# Drive_Board_Schematic_3_motors_SchDocFin.net
KiCad netlist of a schematic drawn in Altium Designer
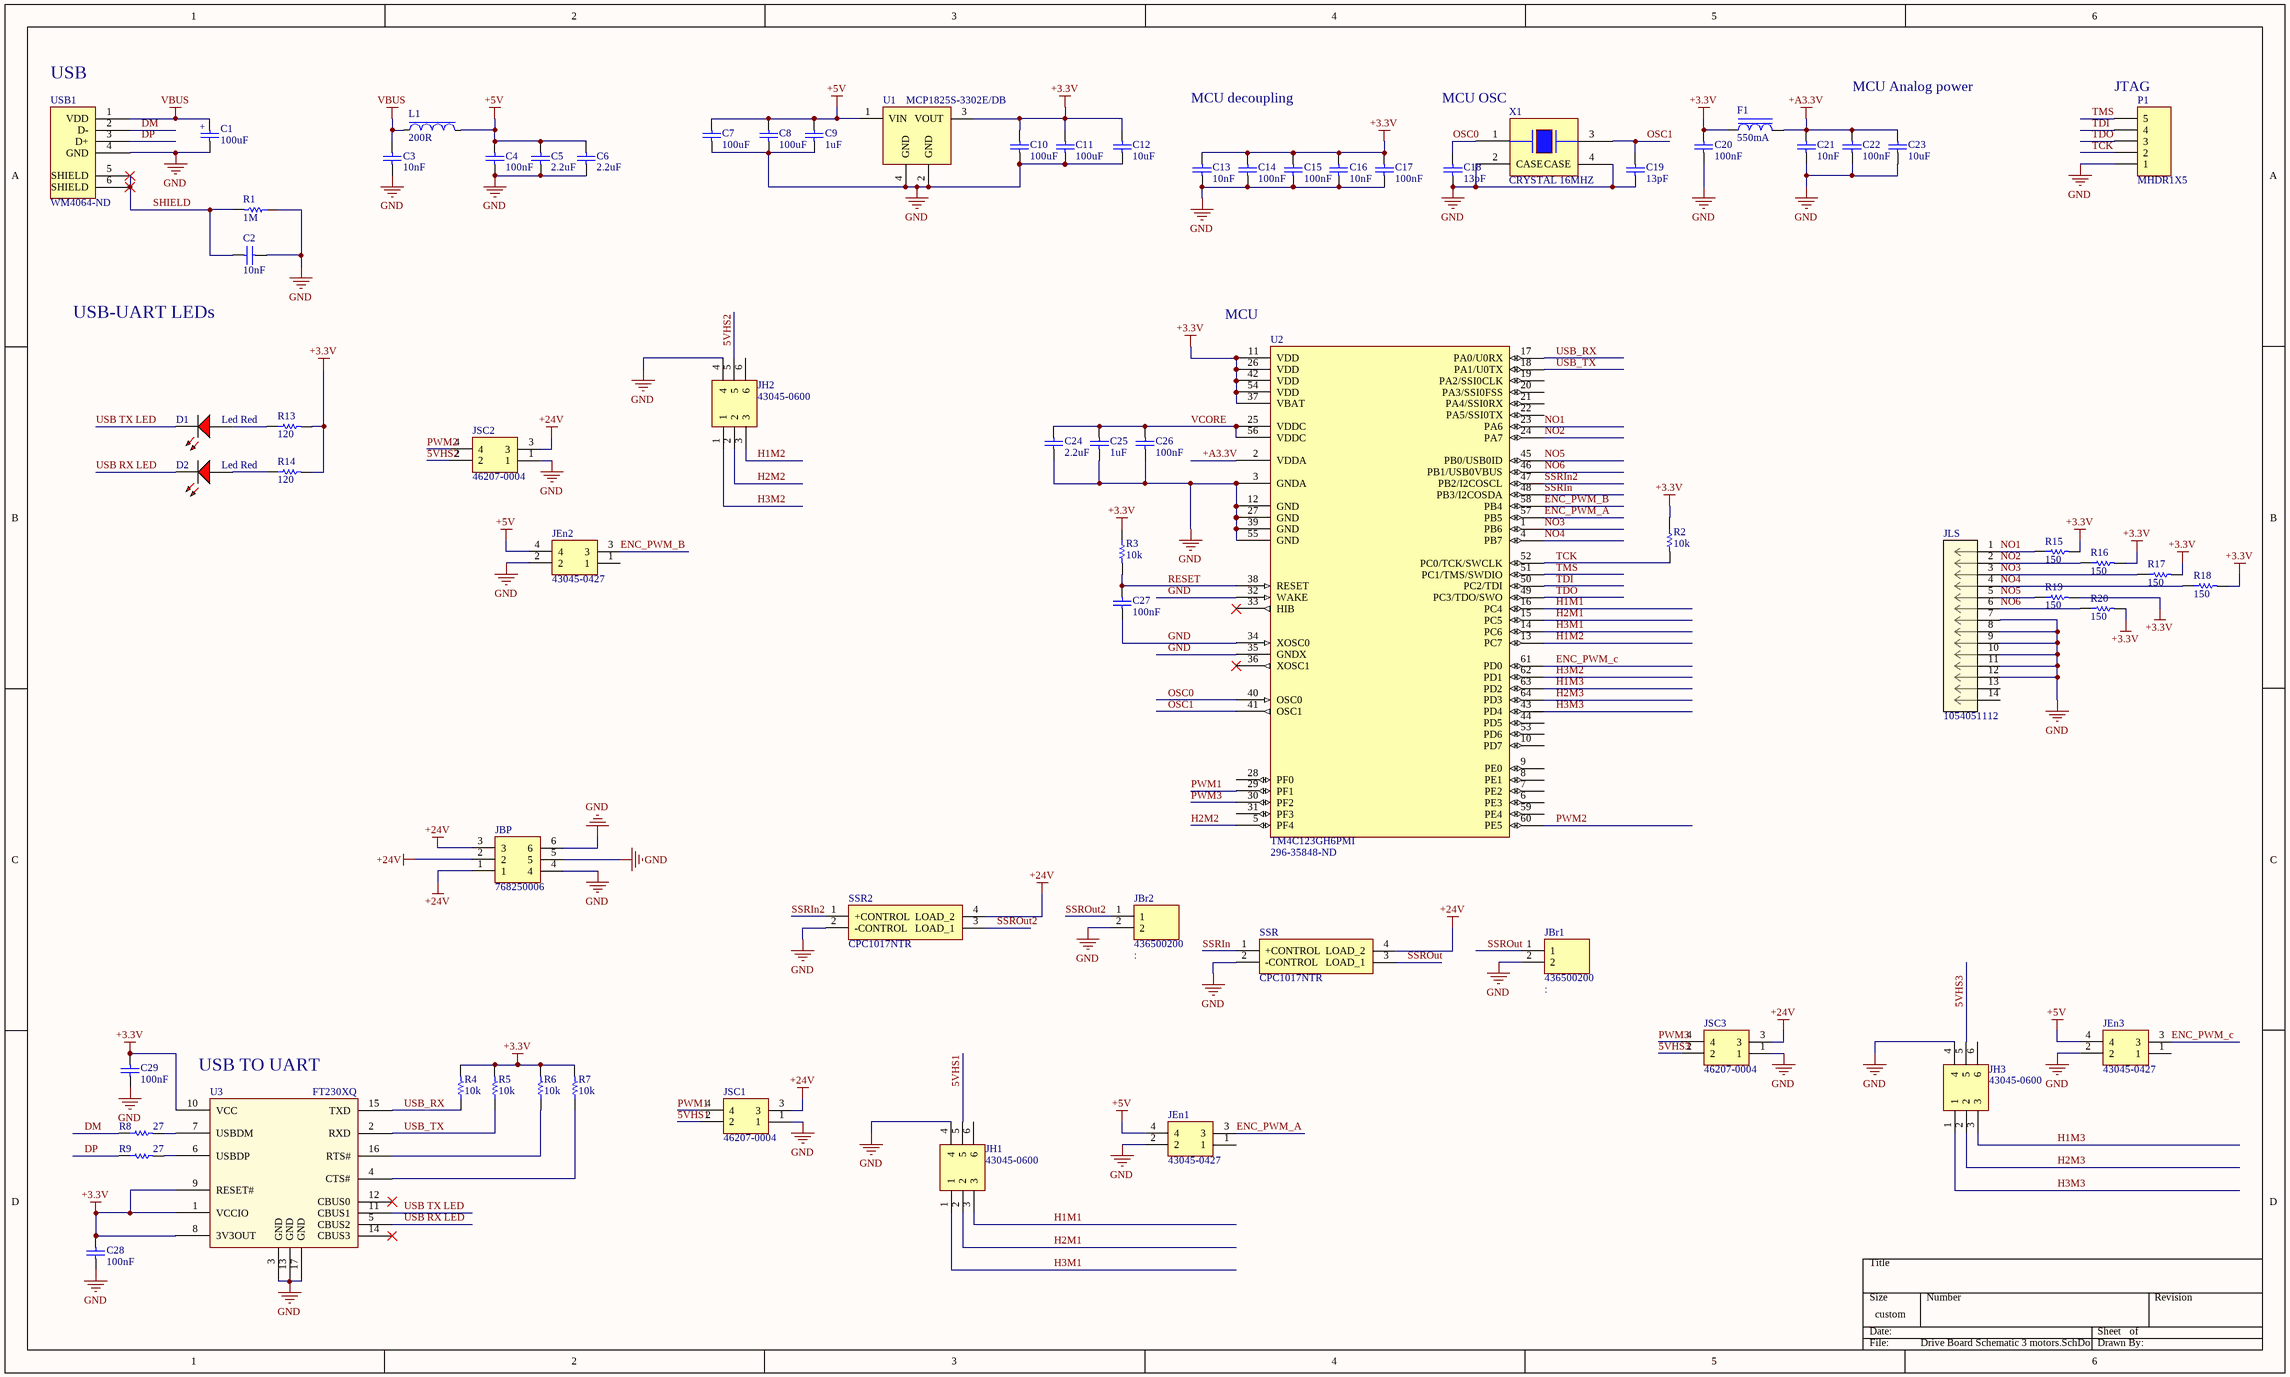
[diagram p0: Drive Board Schematic 3 motors.SchDocFinal.SchDoc]

(export (version "E")
  (design (tool "Eeschema 10.0.6"))
  (components
    (comp (ref "C1")
      (value "100uF")
      (footprint "CapAlu6.3mmx12.5mm")
      (description "Capacitor 35v 100uF 6.3mm")
      (fields
        (field (name "MANUFACTURER") "Nichicon")
        (field (name "MANUFACTURER PART NUMBER") "UHV1V101MED")
      )
      (libsource (lib "Capacitors") (part "100uF_35v_6.3x12.5"))
    )
    (comp (ref "C2")
      (value "10nF")
      (footprint "CAP_1206")
      (description "CAP CER 10000PF 500V X7R 1206")
      (fields
        (field (name "MANUFACTURER") "Samsung Electro-Mechanics America, Inc")
        (field (name "MANUFACTURER PART NUMBER") "CL31B103KGFNNNE")
      )
      (libsource (lib "Capacitors") (part "10nF_500V_1206"))
    )
    (comp (ref "C3")
      (value "10nF")
      (footprint "CAP_0402_M")
      (description "CAP CER 10000PF 50V 10% X7R 0402")
      (fields
        (field (name "MANUFACTURER") "Kemet")
        (field (name "MANUFACTURER PART NUMBER") "C0402C103K5RACTU")
      )
      (libsource (lib "Capacitors") (part "10nF_50V_0402"))
    )
    (comp (ref "C4")
      (value "100nF")
      (footprint "CAP_0402_M")
      (description "CAP CER 100NF 50V 20% X5R 0402")
      (fields
        (field (name "MANUFACTURER") "TDK Corporation")
        (field (name "MANUFACTURER PART NUMBER") "C1005X5R1H104M050BB")
      )
      (libsource (lib "Capacitors") (part "100nF_50V_0402"))
    )
    (comp (ref "C5")
      (value "2.2uF")
      (footprint "CAP_0402_M")
      (description "CAP CER 2.2UF 10V 20% X5R 0402")
      (fields
        (field (name "MANUFACTURER") "Taiyo Yuden")
        (field (name "MANUFACTURER PART NUMBER") "LMK105BJ225MV-F")
      )
      (libsource (lib "Capacitors") (part "2.2uF_10V_0402"))
    )
    (comp (ref "C6")
      (value "2.2uF")
      (footprint "CAP_0402_M")
      (description "CAP CER 2.2UF 10V 20% X5R 0402")
      (fields
        (field (name "MANUFACTURER") "Taiyo Yuden")
        (field (name "MANUFACTURER PART NUMBER") "LMK105BJ225MV-F")
      )
      (libsource (lib "Capacitors") (part "2.2uF_10V_0402"))
    )
    (comp (ref "C7")
      (value "100uF")
      (footprint "CAP_1206")
      (description "CAP CER 100UF 6.3V X5R 1206")
      (fields
        (field (name "MANUFACTURER") "Murata Electronics North America")
        (field (name "MANUFACTURER PART NUMBER") "GRM31CR60J107ME39L")
      )
      (libsource (lib "Capacitors") (part "100uF_6.3v_1206_X5R"))
    )
    (comp (ref "C8")
      (value "100uF")
      (footprint "CAP_1206")
      (description "CAP CER 100UF 6.3V X5R 1206")
      (fields
        (field (name "MANUFACTURER") "Murata Electronics North America")
        (field (name "MANUFACTURER PART NUMBER") "GRM31CR60J107ME39L")
      )
      (libsource (lib "Capacitors") (part "100uF_6.3v_1206_X5R"))
    )
    (comp (ref "C9")
      (value "1uF")
      (footprint "CAP_0402_M")
      (description "CAP CER 1UF 25V 10% X5R 0402")
      (fields
        (field (name "MANUFACTURER") "TDK Corporation")
        (field (name "MANUFACTURER PART NUMBER") "C1005X5R1E105K050BC")
      )
      (libsource (lib "Capacitors") (part "1uF_25V_0402"))
    )
    (comp (ref "C10")
      (value "100uF")
      (footprint "CAP_1206")
      (description "CAP CER 100UF 6.3V X5R 1206")
      (fields
        (field (name "MANUFACTURER") "Murata Electronics North America")
        (field (name "MANUFACTURER PART NUMBER") "GRM31CR60J107ME39L")
      )
      (libsource (lib "Capacitors") (part "100uF_6.3v_1206_X5R"))
    )
    (comp (ref "C11")
      (value "100uF")
      (footprint "CAP_1206")
      (description "CAP CER 100UF 6.3V X5R 1206")
      (fields
        (field (name "MANUFACTURER") "Murata Electronics North America")
        (field (name "MANUFACTURER PART NUMBER") "GRM31CR60J107ME39L")
      )
      (libsource (lib "Capacitors") (part "100uF_6.3v_1206_X5R"))
    )
    (comp (ref "C12")
      (value "10uF")
      (footprint "CAP_0603")
      (description "CAP CER 10UF 10V 20% X5R 0603")
      (fields
        (field (name "MANUFACTURER") "Taiyo Yuden")
        (field (name "MANUFACTURER PART NUMBER") "LMK107BBJ106MAHT")
      )
      (libsource (lib "Capacitors") (part "10uF_10V_0603"))
    )
    (comp (ref "C13")
      (value "10nF")
      (footprint "CAP_0402_M")
      (description "CAP CER 10000PF 50V 10% X7R 0402")
      (fields
        (field (name "MANUFACTURER") "Kemet")
        (field (name "MANUFACTURER PART NUMBER") "C0402C103K5RACTU")
      )
      (libsource (lib "Capacitors") (part "10nF_50V_0402"))
    )
    (comp (ref "C14")
      (value "100nF")
      (footprint "CAP_0402_M")
      (description "CAP CER 100NF 50V 20% X5R 0402")
      (fields
        (field (name "MANUFACTURER") "TDK Corporation")
        (field (name "MANUFACTURER PART NUMBER") "C1005X5R1H104M050BB")
      )
      (libsource (lib "Capacitors") (part "100nF_50V_0402"))
    )
    (comp (ref "C15")
      (value "100nF")
      (footprint "CAP_0402_M")
      (description "CAP CER 100NF 50V 20% X5R 0402")
      (fields
        (field (name "MANUFACTURER") "TDK Corporation")
        (field (name "MANUFACTURER PART NUMBER") "C1005X5R1H104M050BB")
      )
      (libsource (lib "Capacitors") (part "100nF_50V_0402"))
    )
    (comp (ref "C16")
      (value "10nF")
      (footprint "CAP_0402_M")
      (description "CAP CER 10000PF 50V 10% X7R 0402")
      (fields
        (field (name "MANUFACTURER") "Kemet")
        (field (name "MANUFACTURER PART NUMBER") "C0402C103K5RACTU")
      )
      (libsource (lib "Capacitors") (part "10nF_50V_0402"))
    )
    (comp (ref "C17")
      (value "100nF")
      (footprint "CAP_0402_M")
      (description "CAP CER 100NF 50V 20% X5R 0402")
      (fields
        (field (name "MANUFACTURER") "TDK Corporation")
        (field (name "MANUFACTURER PART NUMBER") "C1005X5R1H104M050BB")
      )
      (libsource (lib "Capacitors") (part "100nF_50V_0402"))
    )
    (comp (ref "C18")
      (value "13pF")
      (footprint "CAP_0402_M")
      (description "CAP CER 13PF 50V 5% NP0 0402")
      (fields
        (field (name "MANUFACTURER") "Samsung Electro-Mechanics America, Inc")
        (field (name "MANUFACTURER PART NUMBER") "CL05C130JB5NNNC")
      )
      (libsource (lib "Capacitors") (part "13pF_50V_0402"))
    )
    (comp (ref "C19")
      (value "13pF")
      (footprint "CAP_0402_M")
      (description "CAP CER 13PF 50V 5% NP0 0402")
      (fields
        (field (name "MANUFACTURER") "Samsung Electro-Mechanics America, Inc")
        (field (name "MANUFACTURER PART NUMBER") "CL05C130JB5NNNC")
      )
      (libsource (lib "Capacitors") (part "13pF_50V_0402"))
    )
    (comp (ref "C20")
      (value "100nF")
      (footprint "CAP_0402_M")
      (description "CAP CER 100NF 50V 20% X5R 0402")
      (fields
        (field (name "MANUFACTURER") "TDK Corporation")
        (field (name "MANUFACTURER PART NUMBER") "C1005X5R1H104M050BB")
      )
      (libsource (lib "Capacitors") (part "100nF_50V_0402"))
    )
    (comp (ref "C21")
      (value "10nF")
      (footprint "CAP_0402_M")
      (description "CAP CER 10000PF 50V 10% X7R 0402")
      (fields
        (field (name "MANUFACTURER") "Kemet")
        (field (name "MANUFACTURER PART NUMBER") "C0402C103K5RACTU")
      )
      (libsource (lib "Capacitors") (part "10nF_50V_0402"))
    )
    (comp (ref "C22")
      (value "100nF")
      (footprint "CAP_0402_M")
      (description "CAP CER 100NF 50V 20% X5R 0402")
      (fields
        (field (name "MANUFACTURER") "TDK Corporation")
        (field (name "MANUFACTURER PART NUMBER") "C1005X5R1H104M050BB")
      )
      (libsource (lib "Capacitors") (part "100nF_50V_0402"))
    )
    (comp (ref "C23")
      (value "10uF")
      (footprint "CAP_0603")
      (description "CAP CER 10UF 10V 20% X5R 0603")
      (fields
        (field (name "MANUFACTURER") "Taiyo Yuden")
        (field (name "MANUFACTURER PART NUMBER") "LMK107BBJ106MAHT")
      )
      (libsource (lib "Capacitors") (part "10uF_10V_0603"))
    )
    (comp (ref "C24")
      (value "2.2uF")
      (footprint "CAP_0603")
      (description "CAP CER 2.2UF 35V 10% X5R 0603")
      (fields
        (field (name "MANUFACTURER") "Murata Electronics North America")
        (field (name "MANUFACTURER PART NUMBER") "GRM188R6YA225KA12D")
      )
      (libsource (lib "Capacitors") (part "2.2uF_35V_0603"))
    )
    (comp (ref "C25")
      (value "1uF")
      (footprint "CAP_0402_M")
      (description "CAP CER 1UF 25V 10% X5R 0402")
      (fields
        (field (name "MANUFACTURER") "TDK Corporation")
        (field (name "MANUFACTURER PART NUMBER") "C1005X5R1E105K050BC")
      )
      (libsource (lib "Capacitors") (part "1uF_25V_0402"))
    )
    (comp (ref "C26")
      (value "100nF")
      (footprint "CAP_0402_M")
      (description "CAP CER 100NF 50V 20% X5R 0402")
      (fields
        (field (name "MANUFACTURER") "TDK Corporation")
        (field (name "MANUFACTURER PART NUMBER") "C1005X5R1H104M050BB")
      )
      (libsource (lib "Capacitors") (part "100nF_50V_0402"))
    )
    (comp (ref "C27")
      (value "100nF")
      (footprint "CAP_0402_M")
      (description "CAP CER 100NF 50V 20% X5R 0402")
      (fields
        (field (name "MANUFACTURER") "TDK Corporation")
        (field (name "MANUFACTURER PART NUMBER") "C1005X5R1H104M050BB")
      )
      (libsource (lib "Capacitors") (part "100nF_50V_0402"))
    )
    (comp (ref "C28")
      (value "100nF")
      (footprint "CAP_0402_M")
      (description "CAP CER 100NF 50V 20% X5R 0402")
      (fields
        (field (name "MANUFACTURER") "TDK Corporation")
        (field (name "MANUFACTURER PART NUMBER") "C1005X5R1H104M050BB")
      )
      (libsource (lib "Capacitors") (part "100nF_50V_0402"))
    )
    (comp (ref "C29")
      (value "100nF")
      (footprint "CAP_0402_M")
      (description "CAP CER 100NF 50V 20% X5R 0402")
      (fields
        (field (name "MANUFACTURER") "TDK Corporation")
        (field (name "MANUFACTURER PART NUMBER") "C1005X5R1H104M050BB")
      )
      (libsource (lib "Capacitors") (part "100nF_50V_0402"))
    )
    (comp (ref "D1")
      (value "Led Red")
      (footprint "TOPLED 0805")
      (description "LED TOPLED 630NM SUP RED CLR SMD")
      (fields
        (field (name "MANUFACTURER") "OSRAM Opto Semiconductors Inc")
        (field (name "MANUFACTURER PART NUMBER") "LS M67K-H2L1-1-Z")
      )
      (libsource (lib "Diodes") (part "TOPLED 0803"))
    )
    (comp (ref "D2")
      (value "Led Red")
      (footprint "TOPLED 0805")
      (description "LED TOPLED 630NM SUP RED CLR SMD")
      (fields
        (field (name "MANUFACTURER") "OSRAM Opto Semiconductors Inc")
        (field (name "MANUFACTURER PART NUMBER") "LS M67K-H2L1-1-Z")
      )
      (libsource (lib "Diodes") (part "TOPLED 0803"))
    )
    (comp (ref "F1")
      (value "550mA")
      (footprint "RES_0402_M")
      (description "FERRITE CHIP 40 OHM 550MA 0402")
      (fields
        (field (name "MANUFACTURER") "TDK Corporation")
        (field (name "MANUFACTURER PART NUMBER") "MMZ1005Y400CT000")
      )
      (libsource (lib "Resistors") (part "40O_550mA_0402"))
    )
    (comp (ref "JBP")
      (value "768250006")
      (footprint "SamacSys:768250006")
      (description "Connector")
      (libsource (lib "*") (part "768250006"))
    )
    (comp (ref "JBr1")
      (value "436500200")
      (footprint "MOLEX_436500200")
      (description "Connector Header Through Hole, Right Angle 2 position 0.118 (3.00mm)")
      (fields (field (name "MF") "Molex"))
      (libsource (lib "436500200") (part "436500200"))
    )
    (comp (ref "JBr2")
      (value "436500200")
      (footprint "MOLEX_436500200")
      (description "Connector Header Through Hole, Right Angle 2 position 0.118 (3.00mm)")
      (fields (field (name "MF") "Molex"))
      (libsource (lib "436500200") (part "436500200"))
    )
    (comp (ref "JEn1")
      (value "43045-0427")
      (footprint "SamacSys:43045-0428")
      (description "Connector")
      (fields (field (name "MOUSER PART NUMBER") "538-43045-0427"))
      (libsource (lib "SamacSys") (part "43045-0427"))
    )
    (comp (ref "JEn2")
      (value "43045-0427")
      (footprint "SamacSys:43045-0428")
      (description "Connector")
      (fields (field (name "MOUSER PART NUMBER") "538-43045-0427"))
      (libsource (lib "SamacSys") (part "43045-0427"))
    )
    (comp (ref "JEn3")
      (value "43045-0427")
      (footprint "SamacSys:43045-0428")
      (description "Connector")
      (fields (field (name "MOUSER PART NUMBER") "538-43045-0427"))
      (libsource (lib "SamacSys") (part "43045-0427"))
    )
    (comp (ref "JH1")
      (value "43045-0600")
      (footprint "SamacSys:43045-0600")
      (description "Connector")
      (fields (field (name "MOUSER PART NUMBER") "538-43045-0600"))
      (libsource (lib "*") (part "43045-0600"))
    )
    (comp (ref "JH2")
      (value "43045-0600")
      (footprint "SamacSys:43045-0600")
      (description "Connector")
      (fields (field (name "MOUSER PART NUMBER") "538-43045-0600"))
      (libsource (lib "*") (part "43045-0600"))
    )
    (comp (ref "JH3")
      (value "43045-0600")
      (footprint "SamacSys:43045-0600")
      (description "Connector")
      (fields (field (name "MOUSER PART NUMBER") "538-43045-0600"))
      (libsource (lib "*") (part "43045-0600"))
    )
    (comp (ref "JLS")
      (value "1054051112")
      (footprint "CON_1054051112_MOL")
      (description "No Description Available")
      (fields (field (name "COPYRIGHT") "Copyright (C) 2018 Accelerated Designs. All rights reserved"))
      (libsource (lib "Molex 1054051112") (part "1054051112"))
    )
    (comp (ref "JSC1")
      (value "46207-0004")
      (footprint "SamacSys:0462070004")
      (description "Connector")
      (fields (field (name "MOUSER PART NUMBER") "538-46207-0004"))
      (libsource (lib "*") (part "46207-0004"))
    )
    (comp (ref "JSC2")
      (value "46207-0004")
      (footprint "SamacSys:0462070004")
      (description "Connector")
      (fields (field (name "MOUSER PART NUMBER") "538-46207-0004"))
      (libsource (lib "*") (part "46207-0004"))
    )
    (comp (ref "JSC3")
      (value "46207-0004")
      (footprint "SamacSys:0462070004")
      (description "Connector")
      (fields (field (name "MOUSER PART NUMBER") "538-46207-0004"))
      (libsource (lib "*") (part "46207-0004"))
    )
    (comp (ref "L1")
      (value "200R")
      (footprint "IND_0603")
      (description "FILTER CHIP 220 OHM 2A 0603")
      (fields
        (field (name "MANUFACTURER") "Murata Electronics North America")
        (field (name "MANUFACTURER PART NUMBER") "BLM18EG221SN1D")
      )
      (libsource (lib "Inductors") (part "Ferrite_200 ohms_2A"))
    )
    (comp (ref "P1")
      (value "MHDR1X5")
      (footprint "MHDR1X5")
      (description "Header, 5-Pin")
      (fields (field (name "PUBLISHER") "Altium Limited"))
      (libsource (lib "Miscellaneous Connectors") (part "MHDR1X5"))
    )
    (comp (ref "R1")
      (value "1M")
      (footprint "RES_1206")
      (description "RES SMD 1M OHM 5% 1/4W 1206")
      (fields
        (field (name "MANUFACTURER") "Panasonic Electronic Components")
        (field (name "MANUFACTURER PART NUMBER") "ERJ-8GEYJ105V")
      )
      (libsource (lib "Resistors") (part "1M_5%_1206"))
    )
    (comp (ref "R2")
      (value "10k")
      (footprint "RES_0402_M")
      (description "RES SMD 10K OHM 1% 1/10W 0402")
      (fields
        (field (name "MANUFACTURER") "Panasonic Electronic Components")
        (field (name "MANUFACTURER PART NUMBER") "ERJ-2RKF1002X")
      )
      (libsource (lib "Resistors") (part "10k_1%_0402"))
    )
    (comp (ref "R3")
      (value "10k")
      (footprint "RES_0402_M")
      (description "RES SMD 10K OHM 1% 1/10W 0402")
      (fields
        (field (name "MANUFACTURER") "Panasonic Electronic Components")
        (field (name "MANUFACTURER PART NUMBER") "ERJ-2RKF1002X")
      )
      (libsource (lib "Resistors") (part "10k_1%_0402"))
    )
    (comp (ref "R4")
      (value "10k")
      (footprint "RES_0402_M")
      (description "RES SMD 10K OHM 1% 1/10W 0402")
      (fields
        (field (name "MANUFACTURER") "Panasonic Electronic Components")
        (field (name "MANUFACTURER PART NUMBER") "ERJ-2RKF1002X")
      )
      (libsource (lib "Resistors") (part "10k_1%_0402"))
    )
    (comp (ref "R5")
      (value "10k")
      (footprint "RES_0402_M")
      (description "RES SMD 10K OHM 1% 1/10W 0402")
      (fields
        (field (name "MANUFACTURER") "Panasonic Electronic Components")
        (field (name "MANUFACTURER PART NUMBER") "ERJ-2RKF1002X")
      )
      (libsource (lib "Resistors") (part "10k_1%_0402"))
    )
    (comp (ref "R6")
      (value "10k")
      (footprint "RES_0402_M")
      (description "RES SMD 10K OHM 1% 1/10W 0402")
      (fields
        (field (name "MANUFACTURER") "Panasonic Electronic Components")
        (field (name "MANUFACTURER PART NUMBER") "ERJ-2RKF1002X")
      )
      (libsource (lib "Resistors") (part "10k_1%_0402"))
    )
    (comp (ref "R7")
      (value "10k")
      (footprint "RES_0402_M")
      (description "RES SMD 10K OHM 1% 1/10W 0402")
      (fields
        (field (name "MANUFACTURER") "Panasonic Electronic Components")
        (field (name "MANUFACTURER PART NUMBER") "ERJ-2RKF1002X")
      )
      (libsource (lib "Resistors") (part "10k_1%_0402"))
    )
    (comp (ref "R8")
      (value "27")
      (footprint "RES_0402_M")
      (description "RES SMD 27 OHM 1% 1/10W 0402")
      (fields
        (field (name "MANUFACTURER") "Panasonic Electronic Components")
        (field (name "MANUFACTURER PART NUMBER") "ERJ-2RKF27R0X")
      )
      (libsource (lib "Resistors") (part "27_1%_0402"))
    )
    (comp (ref "R9")
      (value "27")
      (footprint "RES_0402_M")
      (description "RES SMD 27 OHM 1% 1/10W 0402")
      (fields
        (field (name "MANUFACTURER") "Panasonic Electronic Components")
        (field (name "MANUFACTURER PART NUMBER") "ERJ-2RKF27R0X")
      )
      (libsource (lib "Resistors") (part "27_1%_0402"))
    )
    (comp (ref "R13")
      (value "120")
      (footprint "RES_0402_M")
      (description "RES SMD 120 OHM 1% 1/10W 0402")
      (fields
        (field (name "MANUFACTURER") "Panasonic Electronic Components")
        (field (name "MANUFACTURER PART NUMBER") "ERJ-2RKF1200X")
      )
      (libsource (lib "Resistors") (part "120_1%_0402"))
    )
    (comp (ref "R14")
      (value "120")
      (footprint "RES_0402_M")
      (description "RES SMD 120 OHM 1% 1/10W 0402")
      (fields
        (field (name "MANUFACTURER") "Panasonic Electronic Components")
        (field (name "MANUFACTURER PART NUMBER") "ERJ-2RKF1200X")
      )
      (libsource (lib "Resistors") (part "120_1%_0402"))
    )
    (comp (ref "R15")
      (value "150")
      (footprint "RES_0402_M")
      (description "RES SMD 10K OHM 1% 1/10W 0402")
      (fields
        (field (name "MANUFACTURER") "Panasonic Electronic Components")
        (field (name "MANUFACTURER PART NUMBER") "ERJ-2RKF1002X")
      )
      (libsource (lib "Resistors") (part "10k_1%_0402"))
    )
    (comp (ref "R16")
      (value "150")
      (footprint "RES_0402_M")
      (description "RES SMD 10K OHM 1% 1/10W 0402")
      (fields
        (field (name "MANUFACTURER") "Panasonic Electronic Components")
        (field (name "MANUFACTURER PART NUMBER") "ERJ-2RKF1002X")
      )
      (libsource (lib "Resistors") (part "10k_1%_0402"))
    )
    (comp (ref "R17")
      (value "150")
      (footprint "RES_0402_M")
      (description "RES SMD 10K OHM 1% 1/10W 0402")
      (fields
        (field (name "MANUFACTURER") "Panasonic Electronic Components")
        (field (name "MANUFACTURER PART NUMBER") "ERJ-2RKF1002X")
      )
      (libsource (lib "Resistors") (part "10k_1%_0402"))
    )
    (comp (ref "R18")
      (value "150")
      (footprint "RES_0402_M")
      (description "RES SMD 10K OHM 1% 1/10W 0402")
      (fields
        (field (name "MANUFACTURER") "Panasonic Electronic Components")
        (field (name "MANUFACTURER PART NUMBER") "ERJ-2RKF1002X")
      )
      (libsource (lib "Resistors") (part "10k_1%_0402"))
    )
    (comp (ref "R19")
      (value "150")
      (footprint "RES_0402_M")
      (description "RES SMD 10K OHM 1% 1/10W 0402")
      (fields
        (field (name "MANUFACTURER") "Panasonic Electronic Components")
        (field (name "MANUFACTURER PART NUMBER") "ERJ-2RKF1002X")
      )
      (libsource (lib "Resistors") (part "10k_1%_0402"))
    )
    (comp (ref "R20")
      (value "150")
      (footprint "RES_0402_M")
      (description "RES SMD 10K OHM 1% 1/10W 0402")
      (fields
        (field (name "MANUFACTURER") "Panasonic Electronic Components")
        (field (name "MANUFACTURER PART NUMBER") "ERJ-2RKF1002X")
      )
      (libsource (lib "Resistors") (part "10k_1%_0402"))
    )
    (comp (ref "SSR")
      (value "CPC1017NTR")
      (footprint "SamacSys:SOP254P610X216-4N")
      (description "Relay or Contactor")
      (fields (field (name "MOUSER PART NUMBER") "849-CPC1017NTR"))
      (libsource (lib "*") (part "CPC1017NTR"))
    )
    (comp (ref "SSR2")
      (value "CPC1017NTR")
      (footprint "SamacSys:SOP254P610X216-4N")
      (description "Relay or Contactor")
      (fields (field (name "MOUSER PART NUMBER") "849-CPC1017NTR"))
      (libsource (lib "*") (part "CPC1017NTR"))
    )
    (comp (ref "U1")
      (value "MCP1825S-3302E/DB")
      (footprint "SOT230P700X180-4N")
      (description "500 mA, Low Voltage, Low Quiescent Current LDO Regulator")
      (fields (field (name "MANUFACTURER") "Microchip Technology"))
      (libsource (lib "ICs") (part "MCP1825S-3302E/DB"))
    )
    (comp (ref "U2")
      (value "TM4C123GH6PMI")
      (footprint "TSQFP50P1200X1200X120-64N")
      (description "Tiva TM4C123GH6PM Microcontroller ARM Cortex 80 MHz FPU")
      (fields (field (name "SUPPLIER PART NUMBER 1") "296-35848-ND"))
      (libsource (lib "ICs") (part "TM4C123GH6PMI"))
    )
    (comp (ref "U3")
      (value "FT230XQ")
      (footprint "QFN65P400X400X80_HS-17N")
      (description "IC USB SERIAL BASIC UART 16QFN")
      (fields
        (field (name "MANUFACTURER") "FTDI, Future Technology Devices International Ltd")
        (field (name "MANUFACTURER PART NUMBER") "FT230XQ-R")
      )
      (libsource (lib "ICs") (part "FT230XQ-R"))
    )
    (comp (ref "USB1")
      (value "USB type-B jack")
      (footprint "USB2.5-2H4E")
      (fields (field (name "SUPPLIER PART NUMBER 1") "WM4064-ND"))
      (libsource (lib "Connectors") (part "MOLEX 0670688010"))
    )
    (comp (ref "X1")
      (value "CRYSTAL 16MHZ")
      (footprint "CRYSTAL_3.2x2.5")
      (description "CRYSTAL 16MHZ 20PF SMD")
      (fields
        (field (name "MANUFACTURER") "CTS-Frequency Controls")
        (field (name "MANUFACTURER PART NUMBER") "403C35E16M00000")
      )
      (libsource (lib "ICs") (part "403C35E16M00000"))
    )
  )
  (nets
    (net (code "1") (name "+3.3V") (class "Default")
      (node (ref "C10") (pin "1") (pinfunction "1_1") (pintype "passive"))
      (node (ref "C11") (pin "1") (pinfunction "1_1") (pintype "passive"))
      (node (ref "C12") (pin "1") (pinfunction "1_1") (pintype "passive"))
      (node (ref "C13") (pin "2") (pinfunction "2_2") (pintype "passive"))
      (node (ref "C14") (pin "2") (pinfunction "2_2") (pintype "passive"))
      (node (ref "C15") (pin "2") (pinfunction "2_2") (pintype "passive"))
      (node (ref "C16") (pin "2") (pinfunction "2_2") (pintype "passive"))
      (node (ref "C17") (pin "2") (pinfunction "2_2") (pintype "passive"))
      (node (ref "C20") (pin "2") (pinfunction "2_2") (pintype "passive"))
      (node (ref "C28") (pin "2") (pinfunction "2_2") (pintype "passive"))
      (node (ref "C29") (pin "2") (pinfunction "2_2") (pintype "passive"))
      (node (ref "F1") (pin "1") (pinfunction "1_1") (pintype "passive"))
      (node (ref "R13") (pin "2") (pinfunction "2_2") (pintype "passive"))
      (node (ref "R14") (pin "2") (pinfunction "2_2") (pintype "passive"))
      (node (ref "R15") (pin "2") (pinfunction "2_2") (pintype "passive"))
      (node (ref "R16") (pin "2") (pinfunction "2_2") (pintype "passive"))
      (node (ref "R17") (pin "2") (pinfunction "2_2") (pintype "passive"))
      (node (ref "R18") (pin "2") (pinfunction "2_2") (pintype "passive"))
      (node (ref "R19") (pin "2") (pinfunction "2_2") (pintype "passive"))
      (node (ref "R2") (pin "1") (pinfunction "1_1") (pintype "passive"))
      (node (ref "R20") (pin "2") (pinfunction "2_2") (pintype "passive"))
      (node (ref "R3") (pin "1") (pinfunction "1_1") (pintype "passive"))
      (node (ref "R4") (pin "2") (pinfunction "2_2") (pintype "passive"))
      (node (ref "R5") (pin "2") (pinfunction "2_2") (pintype "passive"))
      (node (ref "R6") (pin "2") (pinfunction "2_2") (pintype "passive"))
      (node (ref "R7") (pin "2") (pinfunction "2_2") (pintype "passive"))
      (node (ref "U1") (pin "3") (pinfunction "VOUT_3") (pintype "power_in"))
      (node (ref "U2") (pin "11") (pinfunction "VDD_11") (pintype "power_in"))
      (node (ref "U2") (pin "26") (pinfunction "VDD_26") (pintype "power_in"))
      (node (ref "U2") (pin "37") (pinfunction "VBAT_37") (pintype "power_in"))
      (node (ref "U2") (pin "42") (pinfunction "VDD_42") (pintype "power_in"))
      (node (ref "U2") (pin "54") (pinfunction "VDD_54") (pintype "power_in"))
      (node (ref "U3") (pin "1") (pinfunction "VCCIO_1") (pintype "passive"))
      (node (ref "U3") (pin "10") (pinfunction "VCC_10") (pintype "passive"))
      (node (ref "U3") (pin "8") (pinfunction "3V3OUT_8") (pintype "passive"))
      (node (ref "U3") (pin "9") (pinfunction "RESET#_9") (pintype "passive"))
    )
    (net (code "2") (name "+5V") (class "Default")
      (node (ref "C4") (pin "2") (pinfunction "2_2") (pintype "passive"))
      (node (ref "C5") (pin "2") (pinfunction "2_2") (pintype "passive"))
      (node (ref "C6") (pin "2") (pinfunction "2_2") (pintype "passive"))
      (node (ref "C7") (pin "1") (pinfunction "1_1") (pintype "passive"))
      (node (ref "C8") (pin "1") (pinfunction "1_1") (pintype "passive"))
      (node (ref "C9") (pin "2") (pinfunction "2_2") (pintype "passive"))
      (node (ref "JEn1") (pin "4") (pinfunction "4_4") (pintype "passive"))
      (node (ref "JEn2") (pin "4") (pinfunction "4_4") (pintype "passive"))
      (node (ref "JEn3") (pin "4") (pinfunction "4_4") (pintype "passive"))
      (node (ref "L1") (pin "2") (pinfunction "2_2") (pintype "passive"))
      (node (ref "U1") (pin "1") (pinfunction "VIN_1") (pintype "power_in"))
    )
    (net (code "3") (name "+24V") (class "Default")
      (node (ref "JBP") (pin "1") (pinfunction "1_1") (pintype "passive"))
      (node (ref "JBP") (pin "2") (pinfunction "2_2") (pintype "passive"))
      (node (ref "JBP") (pin "3") (pinfunction "3_3") (pintype "passive"))
      (node (ref "JSC1") (pin "3") (pinfunction "3_3") (pintype "passive"))
      (node (ref "JSC2") (pin "3") (pinfunction "3_3") (pintype "passive"))
      (node (ref "JSC3") (pin "3") (pinfunction "3_3") (pintype "passive"))
      (node (ref "SSR") (pin "4") (pinfunction "LOAD_2_4") (pintype "passive"))
      (node (ref "SSR2") (pin "4") (pinfunction "LOAD_2_4") (pintype "passive"))
    )
    (net (code "4") (name "+A3.3V") (class "Default")
      (node (ref "C21") (pin "2") (pinfunction "2_2") (pintype "passive"))
      (node (ref "C22") (pin "2") (pinfunction "2_2") (pintype "passive"))
      (node (ref "C23") (pin "2") (pinfunction "2_2") (pintype "passive"))
      (node (ref "F1") (pin "2") (pinfunction "2_2") (pintype "passive"))
      (node (ref "U2") (pin "2") (pinfunction "VDDA_2") (pintype "power_in"))
    )
    (net (code "5") (name "/5VHS1") (class "Default")
      (node (ref "JH1") (pin "5") (pinfunction "5_5") (pintype "passive"))
      (node (ref "JSC1") (pin "2") (pinfunction "2_2") (pintype "passive"))
    )
    (net (code "6") (name "/5VHS2") (class "Default")
      (node (ref "JH2") (pin "5") (pinfunction "5_5") (pintype "passive"))
      (node (ref "JSC2") (pin "2") (pinfunction "2_2") (pintype "passive"))
    )
    (net (code "7") (name "/5VHS3") (class "Default")
      (node (ref "JH3") (pin "5") (pinfunction "5_5") (pintype "passive"))
      (node (ref "JSC3") (pin "2") (pinfunction "2_2") (pintype "passive"))
    )
    (net (code "8") (name "/DM") (class "Default")
      (node (ref "R8") (pin "1") (pinfunction "1_1") (pintype "passive"))
      (node (ref "USB1") (pin "2") (pinfunction "D-_2") (pintype "passive"))
    )
    (net (code "9") (name "/DP") (class "Default")
      (node (ref "R9") (pin "1") (pinfunction "1_1") (pintype "passive"))
      (node (ref "USB1") (pin "3") (pinfunction "D+_3") (pintype "passive"))
    )
    (net (code "10") (name "/ENC_PWM_A") (class "Default")
      (node (ref "JEn1") (pin "3") (pinfunction "3_3") (pintype "passive"))
      (node (ref "U2") (pin "57") (pinfunction "PB5_57") (pintype "bidirectional"))
    )
    (net (code "11") (name "/ENC_PWM_B") (class "Default")
      (node (ref "JEn2") (pin "3") (pinfunction "3_3") (pintype "passive"))
      (node (ref "U2") (pin "58") (pinfunction "PB4_58") (pintype "bidirectional"))
    )
    (net (code "12") (name "/ENC_PWM_c") (class "Default")
      (node (ref "JEn3") (pin "3") (pinfunction "3_3") (pintype "passive"))
      (node (ref "U2") (pin "61") (pinfunction "PD0_61") (pintype "bidirectional"))
    )
    (net (code "13") (name "/H1M1") (class "Default")
      (node (ref "JH1") (pin "3") (pinfunction "3_3") (pintype "passive"))
      (node (ref "U2") (pin "16") (pinfunction "PC4_16") (pintype "bidirectional"))
    )
    (net (code "14") (name "/H1M2") (class "Default")
      (node (ref "JH2") (pin "3") (pinfunction "3_3") (pintype "passive"))
      (node (ref "U2") (pin "13") (pinfunction "PC7_13") (pintype "bidirectional"))
    )
    (net (code "15") (name "/H1M3") (class "Default")
      (node (ref "JH3") (pin "3") (pinfunction "3_3") (pintype "passive"))
      (node (ref "U2") (pin "63") (pinfunction "PD2_63") (pintype "bidirectional"))
    )
    (net (code "16") (name "/H2M1") (class "Default")
      (node (ref "JH1") (pin "2") (pinfunction "2_2") (pintype "passive"))
      (node (ref "U2") (pin "15") (pinfunction "PC5_15") (pintype "bidirectional"))
    )
    (net (code "17") (name "/H2M2") (class "Default")
      (node (ref "JH2") (pin "2") (pinfunction "2_2") (pintype "passive"))
      (node (ref "U2") (pin "5") (pinfunction "PF4_5") (pintype "bidirectional"))
    )
    (net (code "18") (name "/H2M3") (class "Default")
      (node (ref "JH3") (pin "2") (pinfunction "2_2") (pintype "passive"))
      (node (ref "U2") (pin "64") (pinfunction "PD3_64") (pintype "bidirectional"))
    )
    (net (code "19") (name "/H3M1") (class "Default")
      (node (ref "JH1") (pin "1") (pinfunction "1_1") (pintype "passive"))
      (node (ref "U2") (pin "14") (pinfunction "PC6_14") (pintype "bidirectional"))
    )
    (net (code "20") (name "/H3M2") (class "Default")
      (node (ref "JH2") (pin "1") (pinfunction "1_1") (pintype "passive"))
      (node (ref "U2") (pin "62") (pinfunction "PD1_62") (pintype "bidirectional"))
    )
    (net (code "21") (name "/H3M3") (class "Default")
      (node (ref "JH3") (pin "1") (pinfunction "1_1") (pintype "passive"))
      (node (ref "U2") (pin "43") (pinfunction "PD4_43") (pintype "bidirectional"))
    )
    (net (code "22") (name "/NO1") (class "Default")
      (node (ref "JLS") (pin "1") (pinfunction "1_1") (pintype "passive"))
      (node (ref "R15") (pin "1") (pinfunction "1_1") (pintype "passive"))
      (node (ref "U2") (pin "23") (pinfunction "PA6_23") (pintype "bidirectional"))
    )
    (net (code "23") (name "/NO2") (class "Default")
      (node (ref "JLS") (pin "2") (pinfunction "2_2") (pintype "passive"))
      (node (ref "R16") (pin "1") (pinfunction "1_1") (pintype "passive"))
      (node (ref "U2") (pin "24") (pinfunction "PA7_24") (pintype "bidirectional"))
    )
    (net (code "24") (name "/NO3") (class "Default")
      (node (ref "JLS") (pin "3") (pinfunction "3_3") (pintype "passive"))
      (node (ref "R17") (pin "1") (pinfunction "1_1") (pintype "passive"))
      (node (ref "U2") (pin "1") (pinfunction "PB6_1") (pintype "bidirectional"))
    )
    (net (code "25") (name "/NO4") (class "Default")
      (node (ref "JLS") (pin "4") (pinfunction "4_4") (pintype "passive"))
      (node (ref "R18") (pin "1") (pinfunction "1_1") (pintype "passive"))
      (node (ref "U2") (pin "4") (pinfunction "PB7_4") (pintype "bidirectional"))
    )
    (net (code "26") (name "/NO5") (class "Default")
      (node (ref "JLS") (pin "5") (pinfunction "5_5") (pintype "passive"))
      (node (ref "R19") (pin "1") (pinfunction "1_1") (pintype "passive"))
      (node (ref "U2") (pin "45") (pinfunction "PB0/USB0ID_45") (pintype "bidirectional"))
    )
    (net (code "27") (name "/NO6") (class "Default")
      (node (ref "JLS") (pin "6") (pinfunction "6_6") (pintype "passive"))
      (node (ref "R20") (pin "1") (pinfunction "1_1") (pintype "passive"))
      (node (ref "U2") (pin "46") (pinfunction "PB1/USB0VBUS_46") (pintype "bidirectional"))
    )
    (net (code "28") (name "/OSC0") (class "Default")
      (node (ref "C18") (pin "2") (pinfunction "2_2") (pintype "passive"))
      (node (ref "U2") (pin "40") (pinfunction "OSC0_40") (pintype "input"))
      (node (ref "X1") (pin "1") (pintype "passive"))
    )
    (net (code "29") (name "/OSC1") (class "Default")
      (node (ref "C19") (pin "2") (pinfunction "2_2") (pintype "passive"))
      (node (ref "U2") (pin "41") (pinfunction "OSC1_41") (pintype "output"))
      (node (ref "X1") (pin "3") (pintype "passive"))
    )
    (net (code "30") (name "/PWM1") (class "Default")
      (node (ref "JSC1") (pin "4") (pinfunction "4_4") (pintype "passive"))
      (node (ref "U2") (pin "29") (pinfunction "PF1_29") (pintype "bidirectional"))
    )
    (net (code "31") (name "/PWM2") (class "Default")
      (node (ref "JSC2") (pin "4") (pinfunction "4_4") (pintype "passive"))
      (node (ref "U2") (pin "60") (pinfunction "PE5_60") (pintype "bidirectional"))
    )
    (net (code "32") (name "/PWM3") (class "Default")
      (node (ref "JSC3") (pin "4") (pinfunction "4_4") (pintype "passive"))
      (node (ref "U2") (pin "30") (pinfunction "PF2_30") (pintype "bidirectional"))
    )
    (net (code "33") (name "/RESET") (class "Default")
      (node (ref "C27") (pin "2") (pinfunction "2_2") (pintype "passive"))
      (node (ref "R3") (pin "2") (pinfunction "2_2") (pintype "passive"))
      (node (ref "U2") (pin "38") (pinfunction "RESET_38") (pintype "input"))
    )
    (net (code "34") (name "/SHIELD") (class "Default")
      (node (ref "C2") (pin "2") (pinfunction "2_2") (pintype "passive"))
      (node (ref "R1") (pin "2") (pinfunction "2_2") (pintype "passive"))
      (node (ref "USB1") (pin "5") (pinfunction "SHIELD_5") (pintype "passive"))
      (node (ref "USB1") (pin "6") (pinfunction "SHIELD_6") (pintype "passive"))
    )
    (net (code "35") (name "/SSRIn") (class "Default")
      (node (ref "SSR") (pin "1") (pinfunction "+CONTROL_1") (pintype "passive"))
      (node (ref "U2") (pin "48") (pinfunction "PB3/I2COSDA_48") (pintype "bidirectional"))
    )
    (net (code "36") (name "/SSRIn2") (class "Default")
      (node (ref "SSR2") (pin "1") (pinfunction "+CONTROL_1") (pintype "passive"))
      (node (ref "U2") (pin "47") (pinfunction "PB2/I2COSCL_47") (pintype "bidirectional"))
    )
    (net (code "37") (name "/SSROut") (class "Default")
      (node (ref "JBr1") (pin "1") (pinfunction "1_1") (pintype "passive"))
      (node (ref "SSR") (pin "3") (pinfunction "LOAD_1_3") (pintype "passive"))
    )
    (net (code "38") (name "/SSROut2") (class "Default")
      (node (ref "JBr2") (pin "1") (pinfunction "1_1") (pintype "passive"))
      (node (ref "SSR2") (pin "3") (pinfunction "LOAD_1_3") (pintype "passive"))
    )
    (net (code "39") (name "/TCK") (class "Default")
      (node (ref "P1") (pin "2") (pinfunction "2_2") (pintype "passive"))
      (node (ref "R2") (pin "2") (pinfunction "2_2") (pintype "passive"))
      (node (ref "U2") (pin "52") (pinfunction "PC0/TCK/SWCLK_52") (pintype "bidirectional"))
    )
    (net (code "40") (name "/TDI") (class "Default")
      (node (ref "P1") (pin "4") (pinfunction "4_4") (pintype "passive"))
      (node (ref "U2") (pin "50") (pinfunction "PC2/TDI_50") (pintype "bidirectional"))
    )
    (net (code "41") (name "/TDO") (class "Default")
      (node (ref "P1") (pin "3") (pinfunction "3_3") (pintype "passive"))
      (node (ref "U2") (pin "49") (pinfunction "PC3/TDO/SWO_49") (pintype "bidirectional"))
    )
    (net (code "42") (name "/TMS") (class "Default")
      (node (ref "P1") (pin "5") (pinfunction "5_5") (pintype "passive"))
      (node (ref "U2") (pin "51") (pinfunction "PC1/TMS/SWDIO_51") (pintype "bidirectional"))
    )
    (net (code "43") (name "/USB RX LED") (class "Default")
      (node (ref "D2") (pin "2") (pinfunction "K_2") (pintype "passive"))
      (node (ref "U3") (pin "5") (pinfunction "CBUS2_5") (pintype "passive"))
    )
    (net (code "44") (name "/USB TX LED") (class "Default")
      (node (ref "D1") (pin "2") (pinfunction "K_2") (pintype "passive"))
      (node (ref "U3") (pin "11") (pinfunction "CBUS1_11") (pintype "passive"))
    )
    (net (code "45") (name "/USB_RX") (class "Default")
      (node (ref "R4") (pin "1") (pinfunction "1_1") (pintype "passive"))
      (node (ref "U2") (pin "17") (pinfunction "PA0/U0RX_17") (pintype "bidirectional"))
      (node (ref "U3") (pin "15") (pinfunction "TXD_15") (pintype "passive"))
    )
    (net (code "46") (name "/USB_TX") (class "Default")
      (node (ref "R5") (pin "1") (pinfunction "1_1") (pintype "passive"))
      (node (ref "U2") (pin "18") (pinfunction "PA1/U0TX_18") (pintype "bidirectional"))
      (node (ref "U3") (pin "2") (pinfunction "RXD_2") (pintype "passive"))
    )
    (net (code "47") (name "/VCORE") (class "Default")
      (node (ref "C24") (pin "2") (pinfunction "2_2") (pintype "passive"))
      (node (ref "C25") (pin "2") (pinfunction "2_2") (pintype "passive"))
      (node (ref "C26") (pin "2") (pinfunction "2_2") (pintype "passive"))
      (node (ref "U2") (pin "25") (pinfunction "VDDC_25") (pintype "power_in"))
      (node (ref "U2") (pin "56") (pinfunction "VDDC_56") (pintype "power_in"))
    )
    (net (code "48") (name "GND") (class "Default")
      (node (ref "C1") (pin "2") (pinfunction "2_2") (pintype "passive"))
      (node (ref "C10") (pin "2") (pinfunction "2_2") (pintype "passive"))
      (node (ref "C11") (pin "2") (pinfunction "2_2") (pintype "passive"))
      (node (ref "C12") (pin "2") (pinfunction "2_2") (pintype "passive"))
      (node (ref "C13") (pin "1") (pinfunction "1_1") (pintype "passive"))
      (node (ref "C14") (pin "1") (pinfunction "1_1") (pintype "passive"))
      (node (ref "C15") (pin "1") (pinfunction "1_1") (pintype "passive"))
      (node (ref "C16") (pin "1") (pinfunction "1_1") (pintype "passive"))
      (node (ref "C17") (pin "1") (pinfunction "1_1") (pintype "passive"))
      (node (ref "C18") (pin "1") (pinfunction "1_1") (pintype "passive"))
      (node (ref "C19") (pin "1") (pinfunction "1_1") (pintype "passive"))
      (node (ref "C2") (pin "1") (pinfunction "1_1") (pintype "passive"))
      (node (ref "C20") (pin "1") (pinfunction "1_1") (pintype "passive"))
      (node (ref "C21") (pin "1") (pinfunction "1_1") (pintype "passive"))
      (node (ref "C22") (pin "1") (pinfunction "1_1") (pintype "passive"))
      (node (ref "C23") (pin "1") (pinfunction "1_1") (pintype "passive"))
      (node (ref "C24") (pin "1") (pinfunction "1_1") (pintype "passive"))
      (node (ref "C25") (pin "1") (pinfunction "1_1") (pintype "passive"))
      (node (ref "C26") (pin "1") (pinfunction "1_1") (pintype "passive"))
      (node (ref "C27") (pin "1") (pinfunction "1_1") (pintype "passive"))
      (node (ref "C28") (pin "1") (pinfunction "1_1") (pintype "passive"))
      (node (ref "C29") (pin "1") (pinfunction "1_1") (pintype "passive"))
      (node (ref "C3") (pin "1") (pinfunction "1_1") (pintype "passive"))
      (node (ref "C4") (pin "1") (pinfunction "1_1") (pintype "passive"))
      (node (ref "C5") (pin "1") (pinfunction "1_1") (pintype "passive"))
      (node (ref "C6") (pin "1") (pinfunction "1_1") (pintype "passive"))
      (node (ref "C7") (pin "2") (pinfunction "2_2") (pintype "passive"))
      (node (ref "C8") (pin "2") (pinfunction "2_2") (pintype "passive"))
      (node (ref "C9") (pin "1") (pinfunction "1_1") (pintype "passive"))
      (node (ref "JBP") (pin "4") (pinfunction "4_4") (pintype "passive"))
      (node (ref "JBP") (pin "5") (pinfunction "5_5") (pintype "passive"))
      (node (ref "JBP") (pin "6") (pinfunction "6_6") (pintype "passive"))
      (node (ref "JBr1") (pin "2") (pinfunction "2_2") (pintype "passive"))
      (node (ref "JBr2") (pin "2") (pinfunction "2_2") (pintype "passive"))
      (node (ref "JEn1") (pin "2") (pinfunction "2_2") (pintype "passive"))
      (node (ref "JEn2") (pin "2") (pinfunction "2_2") (pintype "passive"))
      (node (ref "JEn3") (pin "2") (pinfunction "2_2") (pintype "passive"))
      (node (ref "JH1") (pin "4") (pinfunction "4_4") (pintype "passive"))
      (node (ref "JH2") (pin "4") (pinfunction "4_4") (pintype "passive"))
      (node (ref "JH3") (pin "4") (pinfunction "4_4") (pintype "passive"))
      (node (ref "JLS") (pin "10") (pinfunction "10_10") (pintype "passive"))
      (node (ref "JLS") (pin "11") (pinfunction "11_11") (pintype "passive"))
      (node (ref "JLS") (pin "12") (pinfunction "12_12") (pintype "passive"))
      (node (ref "JLS") (pin "7") (pinfunction "7_7") (pintype "passive"))
      (node (ref "JLS") (pin "8") (pinfunction "8_8") (pintype "passive"))
      (node (ref "JLS") (pin "9") (pinfunction "9_9") (pintype "passive"))
      (node (ref "JSC1") (pin "1") (pinfunction "1_1") (pintype "passive"))
      (node (ref "JSC2") (pin "1") (pinfunction "1_1") (pintype "passive"))
      (node (ref "JSC3") (pin "1") (pinfunction "1_1") (pintype "passive"))
      (node (ref "P1") (pin "1") (pinfunction "1_1") (pintype "passive"))
      (node (ref "R1") (pin "1") (pinfunction "1_1") (pintype "passive"))
      (node (ref "SSR") (pin "2") (pinfunction "-CONTROL_2") (pintype "passive"))
      (node (ref "SSR2") (pin "2") (pinfunction "-CONTROL_2") (pintype "passive"))
      (node (ref "U1") (pin "2") (pinfunction "GND_2") (pintype "power_in"))
      (node (ref "U1") (pin "4") (pinfunction "GND_4") (pintype "power_in"))
      (node (ref "U2") (pin "12") (pinfunction "GND_12") (pintype "power_in"))
      (node (ref "U2") (pin "27") (pinfunction "GND_27") (pintype "power_in"))
      (node (ref "U2") (pin "3") (pinfunction "GNDA_3") (pintype "power_in"))
      (node (ref "U2") (pin "32") (pinfunction "WAKE_32") (pintype "input"))
      (node (ref "U2") (pin "34") (pinfunction "XOSC0_34") (pintype "input"))
      (node (ref "U2") (pin "35") (pinfunction "GNDX_35") (pintype "power_in"))
      (node (ref "U2") (pin "39") (pinfunction "GND_39") (pintype "power_in"))
      (node (ref "U2") (pin "55") (pinfunction "GND_55") (pintype "power_in"))
      (node (ref "U3") (pin "13") (pinfunction "GND_13") (pintype "passive"))
      (node (ref "U3") (pin "17") (pinfunction "GND_17") (pintype "passive"))
      (node (ref "U3") (pin "3") (pinfunction "GND_3") (pintype "passive"))
      (node (ref "USB1") (pin "4") (pinfunction "GND_4") (pintype "power_in"))
      (node (ref "X1") (pin "2") (pinfunction "CASE_2") (pintype "passive"))
      (node (ref "X1") (pin "4") (pinfunction "CASE_4") (pintype "passive"))
    )
    (net (code "49") (name "Net-(D1-A)") (class "Default")
      (node (ref "D1") (pin "1") (pinfunction "A_1") (pintype "passive"))
      (node (ref "R13") (pin "1") (pinfunction "1_1") (pintype "passive"))
    )
    (net (code "50") (name "Net-(D2-A)") (class "Default")
      (node (ref "D2") (pin "1") (pinfunction "A_1") (pintype "passive"))
      (node (ref "R14") (pin "1") (pinfunction "1_1") (pintype "passive"))
    )
    (net (code "51") (name "Net-(U3-CTS#)") (class "Default")
      (node (ref "R7") (pin "1") (pinfunction "1_1") (pintype "passive"))
      (node (ref "U3") (pin "4") (pinfunction "CTS#_4") (pintype "passive"))
    )
    (net (code "52") (name "Net-(U3-RTS#)") (class "Default")
      (node (ref "R6") (pin "1") (pinfunction "1_1") (pintype "passive"))
      (node (ref "U3") (pin "16") (pinfunction "RTS#_16") (pintype "passive"))
    )
    (net (code "53") (name "Net-(U3-USBDM)") (class "Default")
      (node (ref "R8") (pin "2") (pinfunction "2_2") (pintype "passive"))
      (node (ref "U3") (pin "7") (pinfunction "USBDM_7") (pintype "passive"))
    )
    (net (code "54") (name "Net-(U3-USBDP)") (class "Default")
      (node (ref "R9") (pin "2") (pinfunction "2_2") (pintype "passive"))
      (node (ref "U3") (pin "6") (pinfunction "USBDP_6") (pintype "passive"))
    )
    (net (code "55") (name "VBUS") (class "Default")
      (node (ref "C1") (pin "1") (pinfunction "1_1") (pintype "passive"))
      (node (ref "C3") (pin "2") (pinfunction "2_2") (pintype "passive"))
      (node (ref "L1") (pin "1") (pinfunction "1_1") (pintype "passive"))
      (node (ref "USB1") (pin "1") (pinfunction "VDD_1") (pintype "power_in"))
    )
    (net (code "56") (name "unconnected-(JEn1-Pad1)") (class "Default")
      (node (ref "JEn1") (pin "1") (pinfunction "1_1") (pintype "passive"))
    )
    (net (code "57") (name "unconnected-(JEn2-Pad1)") (class "Default")
      (node (ref "JEn2") (pin "1") (pinfunction "1_1") (pintype "passive"))
    )
    (net (code "58") (name "unconnected-(JEn3-Pad1)") (class "Default")
      (node (ref "JEn3") (pin "1") (pinfunction "1_1") (pintype "passive"))
    )
    (net (code "59") (name "unconnected-(JH1-Pad6)") (class "Default")
      (node (ref "JH1") (pin "6") (pinfunction "6_6") (pintype "passive"))
    )
    (net (code "60") (name "unconnected-(JH2-Pad6)") (class "Default")
      (node (ref "JH2") (pin "6") (pinfunction "6_6") (pintype "passive"))
    )
    (net (code "61") (name "unconnected-(JH3-Pad6)") (class "Default")
      (node (ref "JH3") (pin "6") (pinfunction "6_6") (pintype "passive"))
    )
    (net (code "62") (name "unconnected-(JLS-Pad13)") (class "Default")
      (node (ref "JLS") (pin "13") (pinfunction "13_13") (pintype "passive"))
    )
    (net (code "63") (name "unconnected-(JLS-Pad14)") (class "Default")
      (node (ref "JLS") (pin "14") (pinfunction "14_14") (pintype "passive"))
    )
    (net (code "64") (name "unconnected-(U2-HIB-Pad33)") (class "Default")
      (node (ref "U2") (pin "33") (pinfunction "HIB_33") (pintype "output+no_connect"))
    )
    (net (code "65") (name "unconnected-(U2-PA2{slash}SSI0CLK-Pad19)") (class "Default")
      (node (ref "U2") (pin "19") (pinfunction "PA2/SSI0CLK_19") (pintype "bidirectional"))
    )
    (net (code "66") (name "unconnected-(U2-PA3{slash}SSI0FSS-Pad20)") (class "Default")
      (node (ref "U2") (pin "20") (pinfunction "PA3/SSI0FSS_20") (pintype "bidirectional"))
    )
    (net (code "67") (name "unconnected-(U2-PA4{slash}SSI0RX-Pad21)") (class "Default")
      (node (ref "U2") (pin "21") (pinfunction "PA4/SSI0RX_21") (pintype "bidirectional"))
    )
    (net (code "68") (name "unconnected-(U2-PA5{slash}SSI0TX-Pad22)") (class "Default")
      (node (ref "U2") (pin "22") (pinfunction "PA5/SSI0TX_22") (pintype "bidirectional"))
    )
    (net (code "69") (name "unconnected-(U2-PD5-Pad44)") (class "Default")
      (node (ref "U2") (pin "44") (pinfunction "PD5_44") (pintype "bidirectional"))
    )
    (net (code "70") (name "unconnected-(U2-PD6-Pad53)") (class "Default")
      (node (ref "U2") (pin "53") (pinfunction "PD6_53") (pintype "bidirectional"))
    )
    (net (code "71") (name "unconnected-(U2-PD7-Pad10)") (class "Default")
      (node (ref "U2") (pin "10") (pinfunction "PD7_10") (pintype "bidirectional"))
    )
    (net (code "72") (name "unconnected-(U2-PE0-Pad9)") (class "Default")
      (node (ref "U2") (pin "9") (pinfunction "PE0_9") (pintype "bidirectional"))
    )
    (net (code "73") (name "unconnected-(U2-PE1-Pad8)") (class "Default")
      (node (ref "U2") (pin "8") (pinfunction "PE1_8") (pintype "bidirectional"))
    )
    (net (code "74") (name "unconnected-(U2-PE2-Pad7)") (class "Default")
      (node (ref "U2") (pin "7") (pinfunction "PE2_7") (pintype "bidirectional"))
    )
    (net (code "75") (name "unconnected-(U2-PE3-Pad6)") (class "Default")
      (node (ref "U2") (pin "6") (pinfunction "PE3_6") (pintype "bidirectional"))
    )
    (net (code "76") (name "unconnected-(U2-PE4-Pad59)") (class "Default")
      (node (ref "U2") (pin "59") (pinfunction "PE4_59") (pintype "bidirectional"))
    )
    (net (code "77") (name "unconnected-(U2-PF0-Pad28)") (class "Default")
      (node (ref "U2") (pin "28") (pinfunction "PF0_28") (pintype "bidirectional"))
    )
    (net (code "78") (name "unconnected-(U2-PF3-Pad31)") (class "Default")
      (node (ref "U2") (pin "31") (pinfunction "PF3_31") (pintype "bidirectional"))
    )
    (net (code "79") (name "unconnected-(U2-XOSC1-Pad36)") (class "Default")
      (node (ref "U2") (pin "36") (pinfunction "XOSC1_36") (pintype "output+no_connect"))
    )
    (net (code "80") (name "unconnected-(U3-CBUS0-Pad12)") (class "Default")
      (node (ref "U3") (pin "12") (pinfunction "CBUS0_12") (pintype "passive+no_connect"))
    )
    (net (code "81") (name "unconnected-(U3-CBUS3-Pad14)") (class "Default")
      (node (ref "U3") (pin "14") (pinfunction "CBUS3_14") (pintype "passive+no_connect"))
    )
  )
)
